# IoT_Greenhouse_V1_0_A_-_Esp32.net
KiCad netlist of a schematic drawn in Altium Designer
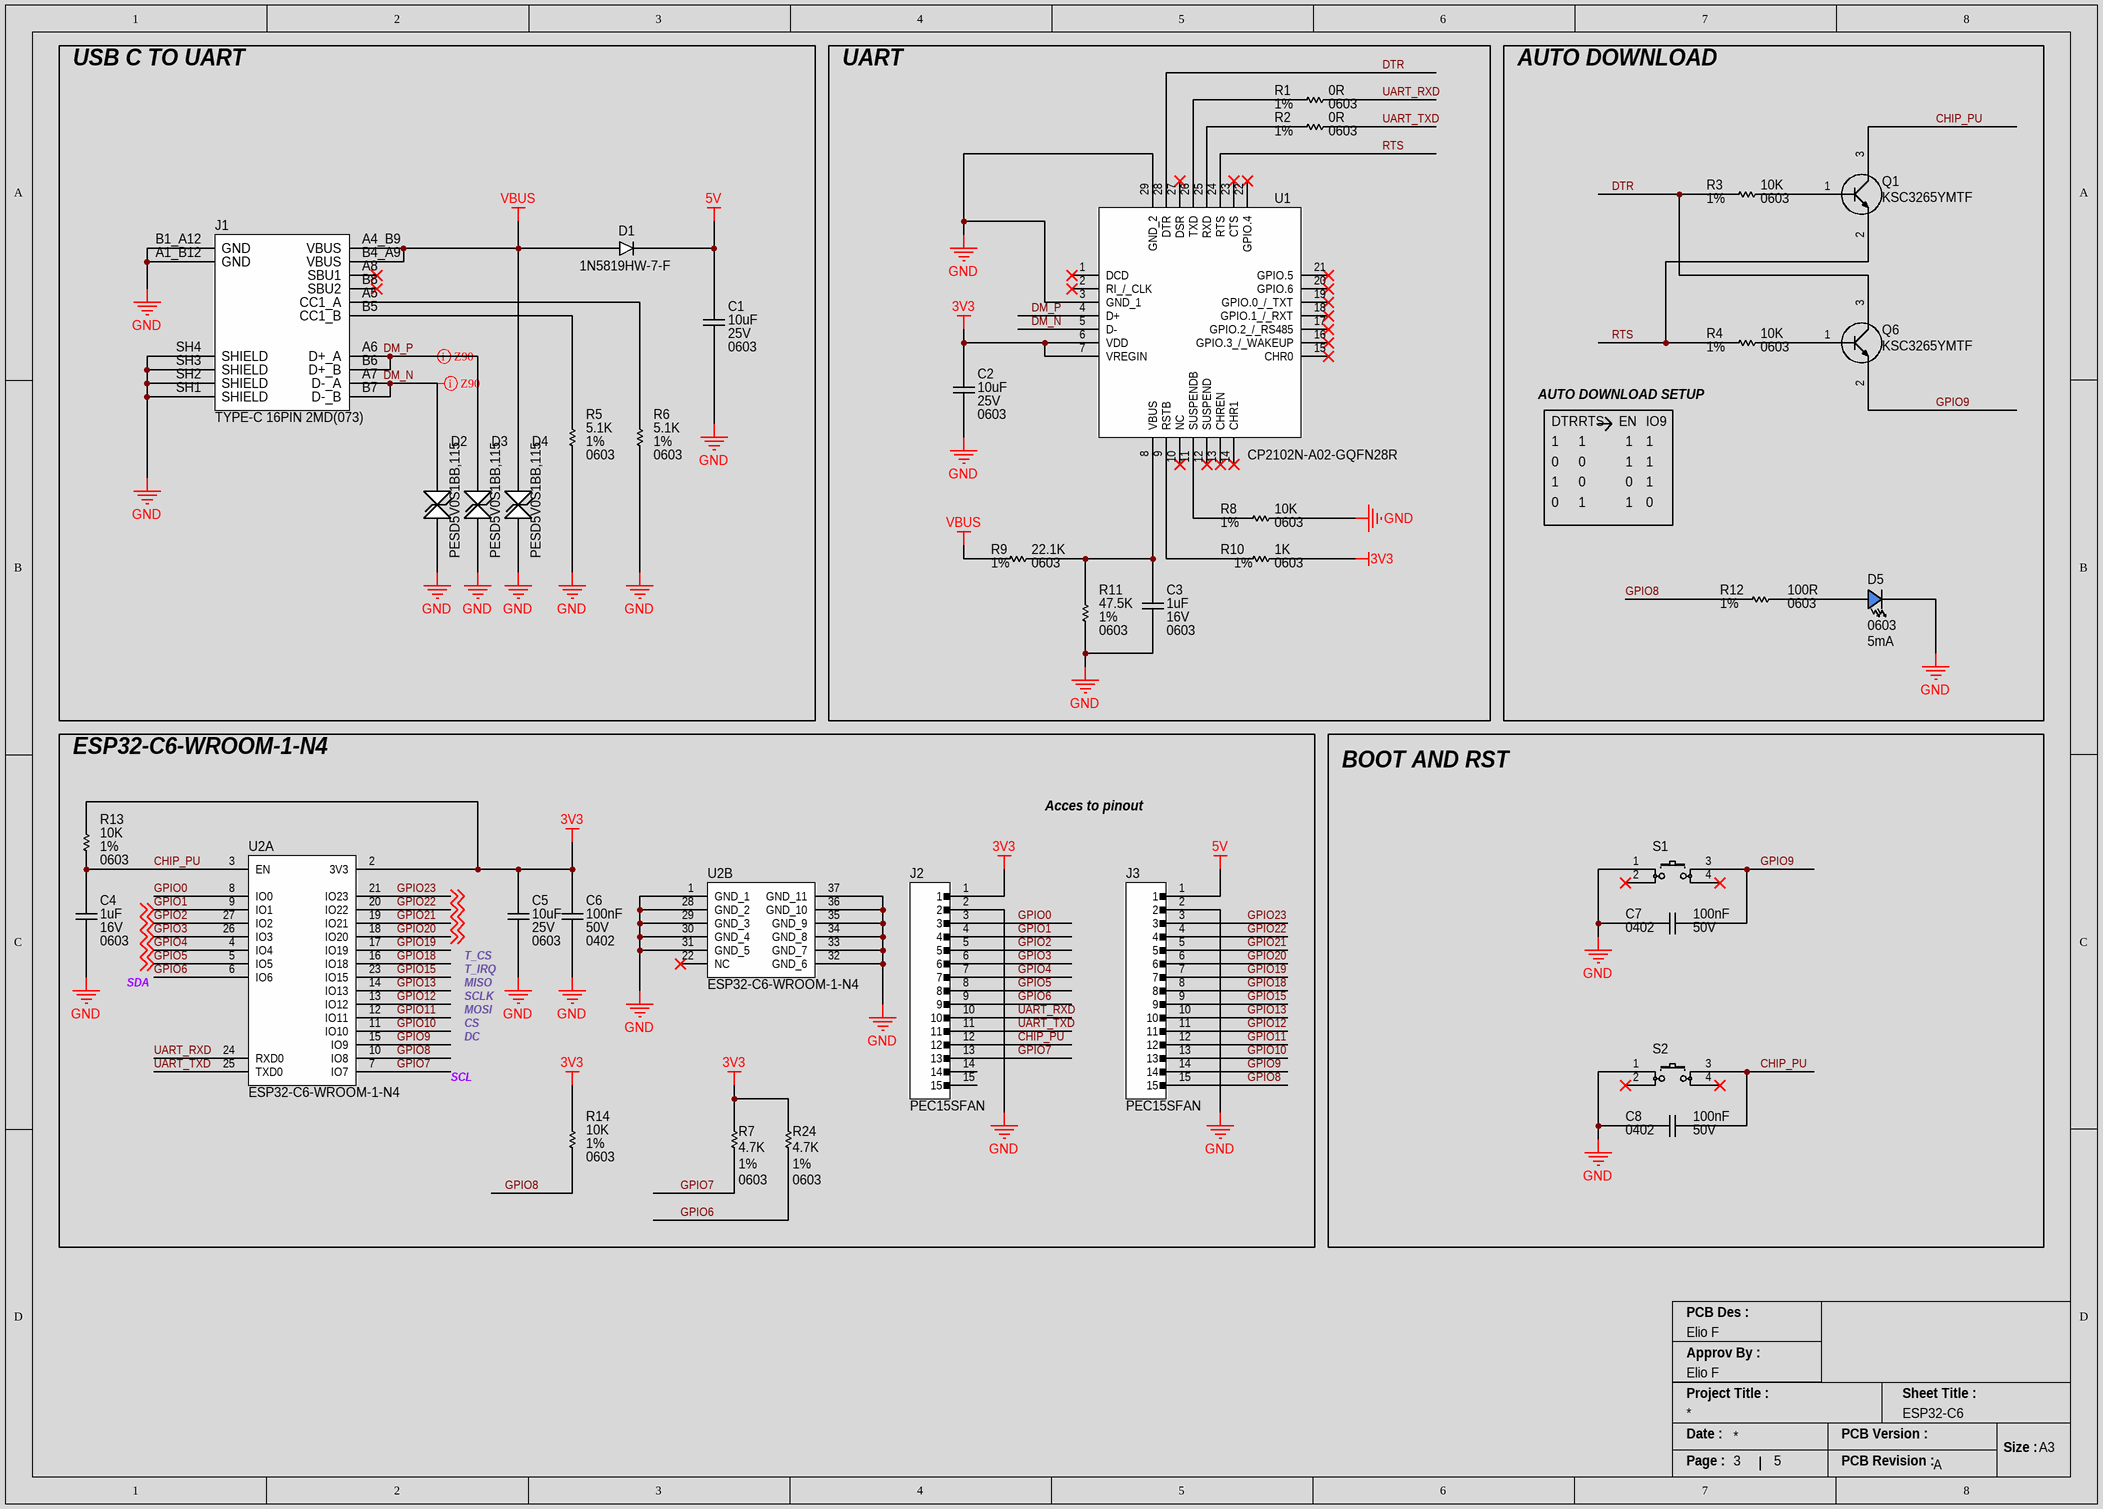
[diagram p0: IoT_Greenhouse V1.0 A - Esp32.SchDoc]

(export (version "E")
  (design (tool "Eeschema 10.0.6"))
  (components
    (comp (ref "C1")
      (value "GRM188R61E106MA73D")
      (footprint "CAP_0603_CAPC1608X08N")
      (description "Multilayer Ceramic Capacitor, 10 uF, 25 V, ± 20%, X5R, 0603 [1608 Metric]")
      (fields
        (field (name "MANUFACTURER") "Murata")
        (field (name "TOLERANCE") "20%")
        (field (name "CASE/PACKAGE") "0603")
        (field (name "CAPACITANCE") "10uF")
        (field (name "VOLTAGE RATING") "25V")
      )
      (libsource (lib "Electronic Devices_LIB") (part "CAP_10UF_25V_X5R_0603"))
    )
    (comp (ref "C2")
      (value "GRM188R61E106MA73D")
      (footprint "CAP_0603_CAPC1608X08N")
      (description "Multilayer Ceramic Capacitor, 10 uF, 25 V, ± 20%, X5R, 0603 [1608 Metric]")
      (fields
        (field (name "MANUFACTURER") "Murata")
        (field (name "TOLERANCE") "20%")
        (field (name "CASE/PACKAGE") "0603")
        (field (name "CAPACITANCE") "10uF")
        (field (name "VOLTAGE RATING") "25V")
      )
      (libsource (lib "Electronic Devices_LIB") (part "CAP_10UF_25V_X5R_0603"))
    )
    (comp (ref "C3")
      (value "CL10A105KO8NNNC")
      (footprint "CAP_0603_CAPC1608X08N")
      (description "CAP CER 1UF 16V X5R 0603")
      (fields
        (field (name "MANUFACTURER") "Samsung")
        (field (name "TOLERANCE") "10%")
        (field (name "VOLTAGE RATING") "16V")
        (field (name "CAPACITANCE") "1uF")
        (field (name "CASE/PACKAGE") "0603")
      )
      (libsource (lib "Electronic Devices_LIB") (part "CAP_1UF_16V_X5R_0603"))
    )
    (comp (ref "C4")
      (value "CL10A105KO8NNNC")
      (footprint "CAP_0603_CAPC1608X08N")
      (description "CAP CER 1UF 16V X5R 0603")
      (fields
        (field (name "MANUFACTURER") "Samsung")
        (field (name "TOLERANCE") "10%")
        (field (name "VOLTAGE RATING") "16V")
        (field (name "CAPACITANCE") "1uF")
        (field (name "CASE/PACKAGE") "0603")
      )
      (libsource (lib "Electronic Devices_LIB") (part "CAP_1UF_16V_X5R_0603"))
    )
    (comp (ref "C5")
      (value "GRM188R61E106MA73D")
      (footprint "CAP_0603_CAPC1608X08N")
      (description "Multilayer Ceramic Capacitor, 10 uF, 25 V, ± 20%, X5R, 0603 [1608 Metric]")
      (fields
        (field (name "MANUFACTURER") "Murata")
        (field (name "TOLERANCE") "20%")
        (field (name "CASE/PACKAGE") "0603")
        (field (name "CAPACITANCE") "10uF")
        (field (name "VOLTAGE RATING") "25V")
      )
      (libsource (lib "Electronic Devices_LIB") (part "CAP_10UF_25V_X5R_0603"))
    )
    (comp (ref "C6")
      (value "GRM155R71H104KE14D")
      (footprint "CAP_0402_CAPC1005X05N")
      (description "Multilayer Ceramic Capacitor, 0.1 uF, 16 V, ± 10%, X7R, 0402 [1005 Metric]")
      (fields
        (field (name "MANUFACTURER") "Murata")
        (field (name "TOLERANCE") "10%")
        (field (name "VOLTAGE RATING") "50V")
        (field (name "CAPACITANCE") "100nF")
        (field (name "CASE/PACKAGE") "0402")
      )
      (libsource (lib "Electronic Devices_LIB") (part "CAP_100NF_50V_X7R_0402"))
    )
    (comp (ref "C7")
      (value "GRM155R71H104KE14D")
      (footprint "CAP_0402_CAPC1005X05N")
      (description "Multilayer Ceramic Capacitor, 0.1 uF, 16 V, ± 10%, X7R, 0402 [1005 Metric]")
      (fields
        (field (name "MANUFACTURER") "Murata")
        (field (name "TOLERANCE") "10%")
        (field (name "VOLTAGE RATING") "50V")
        (field (name "CAPACITANCE") "100nF")
        (field (name "CASE/PACKAGE") "0402")
      )
      (libsource (lib "Electronic Devices_LIB") (part "CAP_100NF_50V_X7R_0402"))
    )
    (comp (ref "C8")
      (value "GRM155R71H104KE14D")
      (footprint "CAP_0402_CAPC1005X05N")
      (description "Multilayer Ceramic Capacitor, 0.1 uF, 16 V, ± 10%, X7R, 0402 [1005 Metric]")
      (fields
        (field (name "MANUFACTURER") "Murata")
        (field (name "TOLERANCE") "10%")
        (field (name "VOLTAGE RATING") "50V")
        (field (name "CAPACITANCE") "100nF")
        (field (name "CASE/PACKAGE") "0402")
      )
      (libsource (lib "Electronic Devices_LIB") (part "CAP_100NF_50V_X7R_0402"))
    )
    (comp (ref "D1")
      (value "1N5819HW-7-F")
      (footprint "DIO_SOD3716X145N")
      (description "Rectifier Diode, Schottky, 1 Phase, 1 Element, 1A, 40V V(RRM), Silicon")
      (fields (field (name "MANUFACTURER") "Diodes"))
      (libsource (lib "Electronic Devices_LIB") (part "DIO_RECT_40V_1A_1N5819HW-7-F"))
    )
    (comp (ref "D2")
      (value "PESD5V0S1BB,115")
      (footprint "DIO_TVS_SODFL1608X65N")
      (description "ESD Suppressor Diode TVS Bi-Dir 5V Automotive 2-Pin SOD-523 T/R / TVS DIODE 5VWM 14VC SOD523")
      (fields (field (name "MANUFACTURER") "Nexperia"))
      (libsource (lib "Electronic Devices_LIB") (part "DIO_TVS_BID_5V_PESD5V0S1BB,115"))
    )
    (comp (ref "D3")
      (value "PESD5V0S1BB,115")
      (footprint "DIO_TVS_SODFL1608X65N")
      (description "ESD Suppressor Diode TVS Bi-Dir 5V Automotive 2-Pin SOD-523 T/R / TVS DIODE 5VWM 14VC SOD523")
      (fields (field (name "MANUFACTURER") "Nexperia"))
      (libsource (lib "Electronic Devices_LIB") (part "DIO_TVS_BID_5V_PESD5V0S1BB,115"))
    )
    (comp (ref "D4")
      (value "PESD5V0S1BB,115")
      (footprint "DIO_TVS_SODFL1608X65N")
      (description "ESD Suppressor Diode TVS Bi-Dir 5V Automotive 2-Pin SOD-523 T/R / TVS DIODE 5VWM 14VC SOD523")
      (fields (field (name "MANUFACTURER") "Nexperia"))
      (libsource (lib "Electronic Devices_LIB") (part "DIO_TVS_BID_5V_PESD5V0S1BB,115"))
    )
    (comp (ref "D5")
      (value "LTST-C193TBKT-5A")
      (footprint "LED_0603-BLUE-0.75mm")
      (description "LED Uni-Color Blue 468nm 2-Pin Chip LED T/R")
      (fields
        (field (name "MANUFACTURER") "Vishay Lite-On")
        (field (name "CASE CODE (IMPERIAL)") "0603")
        (field (name "TEST CURRENT") "5mA")
      )
      (libsource (lib "Electronic Devices_LIB") (part "LED_DIO_BLUE_5mA_0603"))
    )
    (comp (ref "J1")
      (value "TYPE-C 16PIN 2MD(073)")
      (footprint "CONN_USB_C_16P")
      (description "5A 1 Surface Mount 16P Female -25℃~+85℃ Type-C SMD USB Connectors ROHS")
      (fields (field (name "MANUFACTURER") "SHOU HAN"))
      (libsource (lib "Electronic Devices_LIB") (part "CONN_USB_TYPEC_2.0_16P_TYPE-C 16PIN 2MD(073)"))
    )
    (comp (ref "J2")
      (value "PEC15SFAN")
      (footprint "HEADER_MALE_15P")
      (description "CONN HEADER .100 SINGL STR 15POS")
      (fields (field (name "MANUFACTURER") "Sullins"))
      (libsource (lib "Electronic Devices_LIB") (part "CONN_HEADER_MALE_15P_2.54mm"))
    )
    (comp (ref "J3")
      (value "PEC15SFAN")
      (footprint "HEADER_MALE_15P")
      (description "CONN HEADER .100 SINGL STR 15POS")
      (fields (field (name "MANUFACTURER") "Sullins"))
      (libsource (lib "Electronic Devices_LIB") (part "CONN_HEADER_MALE_15P_2.54mm"))
    )
    (comp (ref "Q1")
      (value "KSC3265YMTF")
      (footprint "TRANS_BJT_SOT96P237X111-3N")
      (description "KSC3265 Series 25 V CE Breakdown .8 A NPN Epitaxial Silicon Transistor - SOT-23")
      (fields (field (name "MANUFACTURER") "ON Semiconductor / Fairchild"))
      (libsource (lib "Electronic Devices_LIB") (part "TRANS_BJT_NPN_800mA_25V_KSC3265YMTF"))
    )
    (comp (ref "Q6")
      (value "KSC3265YMTF")
      (footprint "TRANS_BJT_SOT96P237X111-3N")
      (description "KSC3265 Series 25 V CE Breakdown .8 A NPN Epitaxial Silicon Transistor - SOT-23")
      (fields (field (name "MANUFACTURER") "ON Semiconductor / Fairchild"))
      (libsource (lib "Electronic Devices_LIB") (part "TRANS_BJT_NPN_800mA_25V_KSC3265YMTF"))
    )
    (comp (ref "R1")
      (value "RC0603FR-070RL")
      (footprint "RES_0603_RESC1608X04N")
      (description "RC Series 0603 0.1 W 0 Ohm Jumper Surface Mount Thick Film Chip Resistor")
      (fields
        (field (name "MANUFACTURER") "Yageo")
        (field (name "TOLERANCE") "1%")
        (field (name "RESISTANCE") "0R")
        (field (name "CASE CODE (IMPERIAL)") "0603")
      )
      (libsource (lib "Electronic Devices_LIB") (part "RES_0R_1%_100mW_0603"))
    )
    (comp (ref "R2")
      (value "RC0603FR-070RL")
      (footprint "RES_0603_RESC1608X04N")
      (description "RC Series 0603 0.1 W 0 Ohm Jumper Surface Mount Thick Film Chip Resistor")
      (fields
        (field (name "MANUFACTURER") "Yageo")
        (field (name "TOLERANCE") "1%")
        (field (name "RESISTANCE") "0R")
        (field (name "CASE CODE (IMPERIAL)") "0603")
      )
      (libsource (lib "Electronic Devices_LIB") (part "RES_0R_1%_100mW_0603"))
    )
    (comp (ref "R3")
      (value "AC0603FR-1010KL")
      (footprint "RES_0603_RESC1608X04N")
      (description "Chip Resistor Automotive Grade Thick Film 0603 10kOhm 1% Paper T/R")
      (fields
        (field (name "MANUFACTURER") "Yageo")
        (field (name "RESISTANCE") "10K")
        (field (name "TOLERANCE") "1%")
        (field (name "CASE/PACKAGE") "0603")
      )
      (libsource (lib "Electronic Devices_LIB") (part "RES_10K_1%_100mW_0603"))
    )
    (comp (ref "R4")
      (value "AC0603FR-1010KL")
      (footprint "RES_0603_RESC1608X04N")
      (description "Chip Resistor Automotive Grade Thick Film 0603 10kOhm 1% Paper T/R")
      (fields
        (field (name "MANUFACTURER") "Yageo")
        (field (name "RESISTANCE") "10K")
        (field (name "TOLERANCE") "1%")
        (field (name "CASE/PACKAGE") "0603")
      )
      (libsource (lib "Electronic Devices_LIB") (part "RES_10K_1%_100mW_0603"))
    )
    (comp (ref "R5")
      (value "RC0603FR-075K1L")
      (footprint "RES_0603_RESC1608X04N")
      (description "SMD Chip Resistor, 5.1 kOhm, ± 1%, 100 mW, 0603 [1608 Metric], Thick Film, General Purpose")
      (fields
        (field (name "MANUFACTURER") "Yageo")
        (field (name "TOLERANCE") "1%")
        (field (name "RESISTANCE") "5.1K")
        (field (name "CASE/PACKAGE") "0603")
      )
      (libsource (lib "Electronic Devices_LIB") (part "RES_5.1K_1%_100mW_0603"))
    )
    (comp (ref "R6")
      (value "RC0603FR-075K1L")
      (footprint "RES_0603_RESC1608X04N")
      (description "SMD Chip Resistor, 5.1 kOhm, ± 1%, 100 mW, 0603 [1608 Metric], Thick Film, General Purpose")
      (fields
        (field (name "MANUFACTURER") "Yageo")
        (field (name "TOLERANCE") "1%")
        (field (name "RESISTANCE") "5.1K")
        (field (name "CASE/PACKAGE") "0603")
      )
      (libsource (lib "Electronic Devices_LIB") (part "RES_5.1K_1%_100mW_0603"))
    )
    (comp (ref "R7")
      (value "RC0603FR-074K7L")
      (footprint "RES_0603_RESC1608X04N")
      (description "Res Thick Film 0603 4.7K Ohm 1% 1/10W ±100ppm/°C Molded SMD Paper T/R")
      (fields
        (field (name "MANUFACTURER") "Yageo")
        (field (name "RESISTANCE") "4.7K")
        (field (name "TOLERANCE") "1%")
        (field (name "CASE/PACKAGE") "0603")
      )
      (libsource (lib "Electronic Devices_LIB") (part "RES_4.7K_1%_100mW_0603"))
    )
    (comp (ref "R8")
      (value "AC0603FR-1010KL")
      (footprint "RES_0603_RESC1608X04N")
      (description "Chip Resistor Automotive Grade Thick Film 0603 10kOhm 1% Paper T/R")
      (fields
        (field (name "MANUFACTURER") "Yageo")
        (field (name "RESISTANCE") "10K")
        (field (name "TOLERANCE") "1%")
        (field (name "CASE/PACKAGE") "0603")
      )
      (libsource (lib "Electronic Devices_LIB") (part "RES_10K_1%_100mW_0603"))
    )
    (comp (ref "R9")
      (value "RC0603FR-0722K1L")
      (footprint "RES_0603_RESC1608X04N")
      (description "SMD Chip Resistor, 22.1 kOhm, ± 1%, 100 mW, 0603 [1608 Metric], Thick Film, General Purpose")
      (fields
        (field (name "MANUFACTURER") "Yageo")
        (field (name "RESISTANCE") "22.1K")
        (field (name "TOLERANCE") "1%")
        (field (name "CASE/PACKAGE") "0603")
      )
      (libsource (lib "Electronic Devices_LIB") (part "RES_22.1K_1%_100mW_0603"))
    )
    (comp (ref "R10")
      (value "AC0603FR-101KL")
      (footprint "RES_0603_RESC1608X04N")
      (description "Chip Resistor Automotive Grade Thick Film 0603 1kOhm 1% Paper T/R")
      (fields
        (field (name "MANUFACTURER") "Yageo")
        (field (name "RESISTANCE") "1K")
        (field (name "TOLERANCE") "1%")
        (field (name "CASE/PACKAGE") "0603")
      )
      (libsource (lib "Electronic Devices_LIB") (part "RES_1K_1%_100mW_0603"))
    )
    (comp (ref "R11")
      (value "AC0603FR-0747K5L")
      (footprint "RES_0603_RESC1608X04N")
      (description "SMD Chip Resistor, 47.5 kOhm, ± 1%, 100 mW, 0603 [1608 Metric], Thick Film, General Purpose")
      (fields
        (field (name "MANUFACTURER") "Yageo")
        (field (name "TOLERANCE") "1%")
        (field (name "RESISTANCE") "47.5K")
        (field (name "CASE/PACKAGE") "0603")
      )
      (libsource (lib "Electronic Devices_LIB") (part "RES_47.5K_1%_100mW_0603"))
    )
    (comp (ref "R12")
      (value "ERJ3EKF1000V")
      (footprint "CAP_0603_CAPC1608X08N")
      (description "Res Thick Film 0603 100 Ohm 1% 1/10W ±100ppm/°C Molded SMD Punched Carrier T/R")
      (fields
        (field (name "MANUFACTURER") "Panasonic")
        (field (name "CASE CODE (IMPERIAL)") "0603")
        (field (name "TOLERANCE") "1%")
        (field (name "RESISTANCE") "100R")
      )
      (libsource (lib "Electronic Devices_LIB") (part "RES_100R_1%_100MW_0603"))
    )
    (comp (ref "R13")
      (value "AC0603FR-1010KL")
      (footprint "RES_0603_RESC1608X04N")
      (description "Chip Resistor Automotive Grade Thick Film 0603 10kOhm 1% Paper T/R")
      (fields
        (field (name "MANUFACTURER") "Yageo")
        (field (name "RESISTANCE") "10K")
        (field (name "TOLERANCE") "1%")
        (field (name "CASE/PACKAGE") "0603")
      )
      (libsource (lib "Electronic Devices_LIB") (part "RES_10K_1%_100mW_0603"))
    )
    (comp (ref "R14")
      (value "AC0603FR-1010KL")
      (footprint "RES_0603_RESC1608X04N")
      (description "Chip Resistor Automotive Grade Thick Film 0603 10kOhm 1% Paper T/R")
      (fields
        (field (name "MANUFACTURER") "Yageo")
        (field (name "RESISTANCE") "10K")
        (field (name "TOLERANCE") "1%")
        (field (name "CASE/PACKAGE") "0603")
      )
      (libsource (lib "Electronic Devices_LIB") (part "RES_10K_1%_100mW_0603"))
    )
    (comp (ref "R24")
      (value "RC0603FR-074K7L")
      (footprint "RES_0603_RESC1608X04N")
      (description "Res Thick Film 0603 4.7K Ohm 1% 1/10W ±100ppm/°C Molded SMD Paper T/R")
      (fields
        (field (name "MANUFACTURER") "Yageo")
        (field (name "RESISTANCE") "4.7K")
        (field (name "TOLERANCE") "1%")
        (field (name "CASE/PACKAGE") "0603")
      )
      (libsource (lib "Electronic Devices_LIB") (part "RES_4.7K_1%_100mW_0603"))
    )
    (comp (ref "S1")
      (value "PTS526SK15SMTR2LFS")
      (footprint "SWT_NO_PTS526SK15SMTR2LFS")
      (description "Switch Tactile N.O. SPST Round Button Gull Wing 0.05A 12VDC 200000Cycles 2.55N SMD T/R")
      (fields (field (name "MANUFACTURER") "ITT C&K"))
      (libsource (lib "Electronic Devices_LIB") (part "SWITCH_NO_SPST_0.05A"))
    )
    (comp (ref "S2")
      (value "PTS526SK15SMTR2LFS")
      (footprint "SWT_NO_PTS526SK15SMTR2LFS")
      (description "Switch Tactile N.O. SPST Round Button Gull Wing 0.05A 12VDC 200000Cycles 2.55N SMD T/R")
      (fields (field (name "MANUFACTURER") "ITT C&K"))
      (libsource (lib "Electronic Devices_LIB") (part "SWITCH_NO_SPST_0.05A"))
    )
    (comp (ref "U1")
      (value "CP2102N-A02-GQFN28R")
      (footprint "IC_BRIDGE_UART_QFN50P500X500X80-29N-D")
      (description "Full Speed USB to UART Bridge USB 2.0 3.3V T/R Automotive 28-Pin QFN EP")
      (fields (field (name "MANUFACTURER") "Silicon Labs"))
      (libsource (lib "Electronic Devices_LIB") (part "IC_BRIDGE_UART_CP2102N-A02-GQFN28R"))
    )
    (comp (ref "U2")
      (value "ESP32-C6-WROOM-1-N4")
      (footprint "IC_MODULE_ESP32C6WROOM1N4")
      (description "ESP32-C6-WROOM-1-N4 Engineering Module - 4 MB Quad SPI Flash")
      (fields (field (name "MANUFACTURER") "Espressif Systems"))
      (libsource (lib "Electronic Devices_LIB") (part "IC_MODULE_ESP32-C6-WROOM-1-N4"))
    )
  )
  (nets
    (net (code "1") (name "/CHIP_PU") (class "Default")
      (node (ref "C4") (pin "2") (pinfunction "2_2") (pintype "passive"))
      (node (ref "C8") (pin "1") (pinfunction "1_1") (pintype "passive"))
      (node (ref "J2") (pin "12") (pinfunction "12_12") (pintype "passive"))
      (node (ref "Q1") (pin "3") (pinfunction "C_3") (pintype "passive"))
      (node (ref "R13") (pin "2") (pinfunction "2_2") (pintype "passive"))
      (node (ref "S2") (pin "3") (pinfunction "NO1_3") (pintype "passive"))
      (node (ref "U2") (pin "3") (pinfunction "EN_3") (pintype "passive"))
    )
    (net (code "2") (name "/DM_N") (class "Default")
      (node (ref "D2") (pin "2") (pinfunction "K2_2") (pintype "passive"))
      (node (ref "J1") (pin "A7") (pinfunction "D-_A_A7") (pintype "passive"))
      (node (ref "J1") (pin "B7") (pinfunction "D-_B_B7") (pintype "passive"))
      (node (ref "U1") (pin "5") (pinfunction "D-_5") (pintype "passive"))
    )
    (net (code "3") (name "/DM_P") (class "Default")
      (node (ref "D3") (pin "2") (pinfunction "K2_2") (pintype "passive"))
      (node (ref "J1") (pin "A6") (pinfunction "D+_A_A6") (pintype "passive"))
      (node (ref "J1") (pin "B6") (pinfunction "D+_B_B6") (pintype "passive"))
      (node (ref "U1") (pin "4") (pinfunction "D+_4") (pintype "passive"))
    )
    (net (code "4") (name "/DTR") (class "Default")
      (node (ref "Q6") (pin "3") (pinfunction "C_3") (pintype "passive"))
      (node (ref "R3") (pin "2") (pinfunction "2_2") (pintype "passive"))
      (node (ref "U1") (pin "28") (pinfunction "DTR_28") (pintype "passive"))
    )
    (net (code "5") (name "/GPIO0") (class "Default")
      (node (ref "J2") (pin "3") (pinfunction "3_3") (pintype "passive"))
      (node (ref "U2") (pin "8") (pinfunction "IO0_8") (pintype "passive"))
    )
    (net (code "6") (name "/GPIO1") (class "Default")
      (node (ref "J2") (pin "4") (pinfunction "4_4") (pintype "passive"))
      (node (ref "J2") (pin "5") (pinfunction "5_5") (pintype "passive"))
      (node (ref "J2") (pin "6") (pinfunction "6_6") (pintype "passive"))
      (node (ref "J2") (pin "7") (pinfunction "7_7") (pintype "passive"))
      (node (ref "J2") (pin "8") (pinfunction "8_8") (pintype "passive"))
      (node (ref "J3") (pin "3") (pinfunction "3_3") (pintype "passive"))
      (node (ref "J3") (pin "4") (pinfunction "4_4") (pintype "passive"))
      (node (ref "J3") (pin "5") (pinfunction "5_5") (pintype "passive"))
      (node (ref "J3") (pin "6") (pinfunction "6_6") (pintype "passive"))
      (node (ref "U2") (pin "18") (pinfunction "IO20_18") (pintype "passive"))
      (node (ref "U2") (pin "19") (pinfunction "IO21_19") (pintype "passive"))
      (node (ref "U2") (pin "20") (pinfunction "IO22_20") (pintype "passive"))
      (node (ref "U2") (pin "21") (pinfunction "IO23_21") (pintype "passive"))
      (node (ref "U2") (pin "26") (pinfunction "IO3_26") (pintype "passive"))
      (node (ref "U2") (pin "27") (pinfunction "IO2_27") (pintype "passive"))
      (node (ref "U2") (pin "4") (pinfunction "IO4_4") (pintype "passive"))
      (node (ref "U2") (pin "5") (pinfunction "IO5_5") (pintype "passive"))
      (node (ref "U2") (pin "9") (pinfunction "IO1_9") (pintype "passive"))
    )
    (net (code "7") (name "/GPIO6") (class "Default")
      (node (ref "J2") (pin "9") (pinfunction "9_9") (pintype "passive"))
      (node (ref "R24") (pin "1") (pinfunction "1_1") (pintype "passive"))
      (node (ref "U2") (pin "6") (pinfunction "IO6_6") (pintype "passive"))
    )
    (net (code "8") (name "/GPIO7") (class "Default")
      (node (ref "J2") (pin "13") (pinfunction "13_13") (pintype "passive"))
      (node (ref "R7") (pin "1") (pinfunction "1_1") (pintype "passive"))
      (node (ref "U2") (pin "7") (pinfunction "IO7_7") (pintype "passive"))
    )
    (net (code "9") (name "/GPIO8") (class "Default")
      (node (ref "J3") (pin "15") (pinfunction "15_15") (pintype "passive"))
      (node (ref "R12") (pin "1") (pinfunction "1_1") (pintype "passive"))
      (node (ref "R14") (pin "2") (pinfunction "2_2") (pintype "passive"))
      (node (ref "U2") (pin "10") (pinfunction "IO8_10") (pintype "passive"))
    )
    (net (code "10") (name "/GPIO9") (class "Default")
      (node (ref "C7") (pin "1") (pinfunction "1_1") (pintype "passive"))
      (node (ref "J3") (pin "14") (pinfunction "14_14") (pintype "passive"))
      (node (ref "Q6") (pin "2") (pinfunction "E_2") (pintype "passive"))
      (node (ref "S1") (pin "3") (pinfunction "NO1_3") (pintype "passive"))
      (node (ref "U2") (pin "15") (pinfunction "IO9_15") (pintype "passive"))
    )
    (net (code "11") (name "/GPIO10") (class "Default")
      (node (ref "J3") (pin "13") (pinfunction "13_13") (pintype "passive"))
      (node (ref "U2") (pin "11") (pinfunction "IO10_11") (pintype "passive"))
    )
    (net (code "12") (name "/GPIO11") (class "Default")
      (node (ref "J3") (pin "12") (pinfunction "12_12") (pintype "passive"))
      (node (ref "U2") (pin "12") (pinfunction "IO11_12") (pintype "passive"))
    )
    (net (code "13") (name "/GPIO12") (class "Default")
      (node (ref "J3") (pin "11") (pinfunction "11_11") (pintype "passive"))
      (node (ref "U2") (pin "13") (pinfunction "IO12_13") (pintype "passive"))
    )
    (net (code "14") (name "/GPIO13") (class "Default")
      (node (ref "J3") (pin "10") (pinfunction "10_10") (pintype "passive"))
      (node (ref "U2") (pin "14") (pinfunction "IO13_14") (pintype "passive"))
    )
    (net (code "15") (name "/GPIO15") (class "Default")
      (node (ref "J3") (pin "9") (pinfunction "9_9") (pintype "passive"))
      (node (ref "U2") (pin "23") (pinfunction "IO15_23") (pintype "passive"))
    )
    (net (code "16") (name "/GPIO18") (class "Default")
      (node (ref "J3") (pin "8") (pinfunction "8_8") (pintype "passive"))
      (node (ref "U2") (pin "16") (pinfunction "IO18_16") (pintype "passive"))
    )
    (net (code "17") (name "/GPIO19") (class "Default")
      (node (ref "J3") (pin "7") (pinfunction "7_7") (pintype "passive"))
      (node (ref "U2") (pin "17") (pinfunction "IO19_17") (pintype "passive"))
    )
    (net (code "18") (name "/RTS") (class "Default")
      (node (ref "Q1") (pin "2") (pinfunction "E_2") (pintype "passive"))
      (node (ref "R4") (pin "2") (pinfunction "2_2") (pintype "passive"))
      (node (ref "U1") (pin "24") (pinfunction "RTS_24") (pintype "passive"))
    )
    (net (code "19") (name "/UART_RXD") (class "Default")
      (node (ref "J2") (pin "10") (pinfunction "10_10") (pintype "passive"))
      (node (ref "R1") (pin "1") (pinfunction "1_1") (pintype "passive"))
      (node (ref "U2") (pin "24") (pinfunction "RXD0_24") (pintype "passive"))
    )
    (net (code "20") (name "/UART_TXD") (class "Default")
      (node (ref "J2") (pin "11") (pinfunction "11_11") (pintype "passive"))
      (node (ref "R2") (pin "1") (pinfunction "1_1") (pintype "passive"))
      (node (ref "U2") (pin "25") (pinfunction "TXD0_25") (pintype "passive"))
    )
    (net (code "21") (name "3V3") (class "Default")
      (node (ref "C2") (pin "2") (pinfunction "2_2") (pintype "passive"))
      (node (ref "C5") (pin "2") (pinfunction "2_2") (pintype "passive"))
      (node (ref "C6") (pin "2") (pinfunction "2_2") (pintype "passive"))
      (node (ref "J2") (pin "1") (pinfunction "1_1") (pintype "passive"))
      (node (ref "R10") (pin "2") (pinfunction "2_2") (pintype "passive"))
      (node (ref "R13") (pin "1") (pinfunction "1_1") (pintype "passive"))
      (node (ref "R14") (pin "1") (pinfunction "1_1") (pintype "passive"))
      (node (ref "R24") (pin "2") (pinfunction "2_2") (pintype "passive"))
      (node (ref "R7") (pin "2") (pinfunction "2_2") (pintype "passive"))
      (node (ref "U1") (pin "6") (pinfunction "VDD_6") (pintype "passive"))
      (node (ref "U1") (pin "7") (pinfunction "VREGIN_7") (pintype "passive"))
      (node (ref "U2") (pin "2") (pinfunction "3V3_2") (pintype "passive"))
    )
    (net (code "22") (name "5V") (class "Default")
      (node (ref "C1") (pin "2") (pinfunction "2_2") (pintype "passive"))
      (node (ref "D1") (pin "1") (pinfunction "K_1") (pintype "passive"))
      (node (ref "J3") (pin "1") (pinfunction "1_1") (pintype "passive"))
    )
    (net (code "23") (name "GND") (class "Default")
      (node (ref "C1") (pin "1") (pinfunction "1_1") (pintype "passive"))
      (node (ref "C2") (pin "1") (pinfunction "1_1") (pintype "passive"))
      (node (ref "C3") (pin "1") (pinfunction "1_1") (pintype "passive"))
      (node (ref "C4") (pin "1") (pinfunction "1_1") (pintype "passive"))
      (node (ref "C5") (pin "1") (pinfunction "1_1") (pintype "passive"))
      (node (ref "C6") (pin "1") (pinfunction "1_1") (pintype "passive"))
      (node (ref "C7") (pin "2") (pinfunction "2_2") (pintype "passive"))
      (node (ref "C8") (pin "2") (pinfunction "2_2") (pintype "passive"))
      (node (ref "D2") (pin "1") (pinfunction "K1_1") (pintype "passive"))
      (node (ref "D3") (pin "1") (pinfunction "K1_1") (pintype "passive"))
      (node (ref "D4") (pin "1") (pinfunction "K1_1") (pintype "passive"))
      (node (ref "D5") (pin "1") (pinfunction "C_1") (pintype "passive"))
      (node (ref "J1") (pin "A1_B12") (pinfunction "GND_A1_B12") (pintype "power_in"))
      (node (ref "J1") (pin "B1_A12") (pinfunction "GND_B1_A12") (pintype "power_in"))
      (node (ref "J1") (pin "SH1") (pinfunction "SHIELD_SH1") (pintype "passive"))
      (node (ref "J1") (pin "SH2") (pinfunction "SHIELD_SH2") (pintype "passive"))
      (node (ref "J1") (pin "SH3") (pinfunction "SHIELD_SH3") (pintype "passive"))
      (node (ref "J1") (pin "SH4") (pinfunction "SHIELD_SH4") (pintype "passive"))
      (node (ref "J2") (pin "2") (pinfunction "2_2") (pintype "passive"))
      (node (ref "J3") (pin "2") (pinfunction "2_2") (pintype "passive"))
      (node (ref "R11") (pin "1") (pinfunction "1_1") (pintype "passive"))
      (node (ref "R5") (pin "1") (pinfunction "1_1") (pintype "passive"))
      (node (ref "R6") (pin "1") (pinfunction "1_1") (pintype "passive"))
      (node (ref "R8") (pin "2") (pinfunction "2_2") (pintype "passive"))
      (node (ref "S1") (pin "1") (pinfunction "COM_1_1") (pintype "passive"))
      (node (ref "S2") (pin "1") (pinfunction "COM_1_1") (pintype "passive"))
      (node (ref "U1") (pin "29") (pinfunction "GND_2_29") (pintype "passive"))
      (node (ref "U1") (pin "3") (pinfunction "GND_1_3") (pintype "passive"))
      (node (ref "U2") (pin "1") (pinfunction "GND_1_1") (pintype "passive"))
      (node (ref "U2") (pin "28") (pinfunction "GND_2_28") (pintype "passive"))
      (node (ref "U2") (pin "29") (pinfunction "GND_3_29") (pintype "passive"))
      (node (ref "U2") (pin "30") (pinfunction "GND_4_30") (pintype "passive"))
      (node (ref "U2") (pin "31") (pinfunction "GND_5_31") (pintype "passive"))
      (node (ref "U2") (pin "32") (pinfunction "GND_6_32") (pintype "passive"))
      (node (ref "U2") (pin "33") (pinfunction "GND_7_33") (pintype "passive"))
      (node (ref "U2") (pin "34") (pinfunction "GND_8_34") (pintype "passive"))
      (node (ref "U2") (pin "35") (pinfunction "GND_9_35") (pintype "passive"))
      (node (ref "U2") (pin "36") (pinfunction "GND_10_36") (pintype "passive"))
      (node (ref "U2") (pin "37") (pinfunction "GND_11_37") (pintype "passive"))
    )
    (net (code "24") (name "Net-(D5-A)") (class "Default")
      (node (ref "D5") (pin "2") (pinfunction "A_2") (pintype "passive"))
      (node (ref "R12") (pin "2") (pinfunction "2_2") (pintype "passive"))
    )
    (net (code "25") (name "Net-(J1-CC1_A)") (class "Default")
      (node (ref "J1") (pin "A5") (pinfunction "CC1_A_A5") (pintype "passive"))
      (node (ref "R6") (pin "2") (pinfunction "2_2") (pintype "passive"))
    )
    (net (code "26") (name "Net-(J1-CC1_B)") (class "Default")
      (node (ref "J1") (pin "B5") (pinfunction "CC1_B_B5") (pintype "passive"))
      (node (ref "R5") (pin "2") (pinfunction "2_2") (pintype "passive"))
    )
    (net (code "27") (name "Net-(Q1-B)") (class "Default")
      (node (ref "Q1") (pin "1") (pinfunction "B_1") (pintype "passive"))
      (node (ref "R3") (pin "1") (pinfunction "1_1") (pintype "passive"))
    )
    (net (code "28") (name "Net-(Q6-B)") (class "Default")
      (node (ref "Q6") (pin "1") (pinfunction "B_1") (pintype "passive"))
      (node (ref "R4") (pin "1") (pinfunction "1_1") (pintype "passive"))
    )
    (net (code "29") (name "Net-(U1-RSTB)") (class "Default")
      (node (ref "R10") (pin "1") (pinfunction "1_1") (pintype "passive"))
      (node (ref "U1") (pin "9") (pinfunction "RSTB_9") (pintype "passive"))
    )
    (net (code "30") (name "Net-(U1-RXD)") (class "Default")
      (node (ref "R2") (pin "2") (pinfunction "2_2") (pintype "passive"))
      (node (ref "U1") (pin "25") (pinfunction "RXD_25") (pintype "passive"))
    )
    (net (code "31") (name "Net-(U1-SUSPENDB)") (class "Default")
      (node (ref "R8") (pin "1") (pinfunction "1_1") (pintype "passive"))
      (node (ref "U1") (pin "11") (pinfunction "SUSPENDB_11") (pintype "passive"))
    )
    (net (code "32") (name "Net-(U1-TXD)") (class "Default")
      (node (ref "R1") (pin "2") (pinfunction "2_2") (pintype "passive"))
      (node (ref "U1") (pin "26") (pinfunction "TXD_26") (pintype "passive"))
    )
    (net (code "33") (name "Net-(U1-VBUS)") (class "Default")
      (node (ref "C3") (pin "2") (pinfunction "2_2") (pintype "passive"))
      (node (ref "R11") (pin "2") (pinfunction "2_2") (pintype "passive"))
      (node (ref "R9") (pin "2") (pinfunction "2_2") (pintype "passive"))
      (node (ref "U1") (pin "8") (pinfunction "VBUS_8") (pintype "passive"))
    )
    (net (code "34") (name "VBUS") (class "Default")
      (node (ref "D1") (pin "2") (pinfunction "A_2") (pintype "passive"))
      (node (ref "D4") (pin "2") (pinfunction "K2_2") (pintype "passive"))
      (node (ref "J1") (pin "A4_B9") (pinfunction "VBUS_A4_B9") (pintype "power_in"))
      (node (ref "J1") (pin "B4_A9") (pinfunction "VBUS_B4_A9") (pintype "power_in"))
      (node (ref "R9") (pin "1") (pinfunction "1_1") (pintype "passive"))
    )
    (net (code "35") (name "unconnected-(J1-SBU1-PadA8)") (class "Default")
      (node (ref "J1") (pin "A8") (pinfunction "SBU1_A8") (pintype "passive+no_connect"))
    )
    (net (code "36") (name "unconnected-(J1-SBU2-PadB8)") (class "Default")
      (node (ref "J1") (pin "B8") (pinfunction "SBU2_B8") (pintype "passive+no_connect"))
    )
    (net (code "37") (name "unconnected-(J2-Pad14)") (class "Default")
      (node (ref "J2") (pin "14") (pinfunction "14_14") (pintype "passive"))
    )
    (net (code "38") (name "unconnected-(J2-Pad15)") (class "Default")
      (node (ref "J2") (pin "15") (pinfunction "15_15") (pintype "passive"))
    )
    (net (code "39") (name "unconnected-(S1-COM2-Pad2)") (class "Default")
      (node (ref "S1") (pin "2") (pinfunction "COM2_2") (pintype "passive+no_connect"))
    )
    (net (code "40") (name "unconnected-(S1-NO2-Pad4)") (class "Default")
      (node (ref "S1") (pin "4") (pinfunction "NO2_4") (pintype "passive+no_connect"))
    )
    (net (code "41") (name "unconnected-(S2-COM2-Pad2)") (class "Default")
      (node (ref "S2") (pin "2") (pinfunction "COM2_2") (pintype "passive+no_connect"))
    )
    (net (code "42") (name "unconnected-(S2-NO2-Pad4)") (class "Default")
      (node (ref "S2") (pin "4") (pinfunction "NO2_4") (pintype "passive+no_connect"))
    )
    (net (code "43") (name "unconnected-(U1-CHR0-Pad15)") (class "Default")
      (node (ref "U1") (pin "15") (pinfunction "CHR0_15") (pintype "passive+no_connect"))
    )
    (net (code "44") (name "unconnected-(U1-CHR1-Pad14)") (class "Default")
      (node (ref "U1") (pin "14") (pinfunction "CHR1_14") (pintype "passive+no_connect"))
    )
    (net (code "45") (name "unconnected-(U1-CHREN-Pad13)") (class "Default")
      (node (ref "U1") (pin "13") (pinfunction "CHREN_13") (pintype "passive+no_connect"))
    )
    (net (code "46") (name "unconnected-(U1-CTS-Pad23)") (class "Default")
      (node (ref "U1") (pin "23") (pinfunction "CTS_23") (pintype "passive+no_connect"))
    )
    (net (code "47") (name "unconnected-(U1-DCD-Pad1)") (class "Default")
      (node (ref "U1") (pin "1") (pinfunction "DCD_1") (pintype "passive+no_connect"))
    )
    (net (code "48") (name "unconnected-(U1-DSR-Pad27)") (class "Default")
      (node (ref "U1") (pin "27") (pinfunction "DSR_27") (pintype "passive+no_connect"))
    )
    (net (code "49") (name "unconnected-(U1-GPIO.0_{slash}_TXT-Pad19)") (class "Default")
      (node (ref "U1") (pin "19") (pinfunction "GPIO.0_/_TXT_19") (pintype "passive+no_connect"))
    )
    (net (code "50") (name "unconnected-(U1-GPIO.1_{slash}_RXT-Pad18)") (class "Default")
      (node (ref "U1") (pin "18") (pinfunction "GPIO.1_/_RXT_18") (pintype "passive+no_connect"))
    )
    (net (code "51") (name "unconnected-(U1-GPIO.2_{slash}_RS485-Pad17)") (class "Default")
      (node (ref "U1") (pin "17") (pinfunction "GPIO.2_/_RS485_17") (pintype "passive+no_connect"))
    )
    (net (code "52") (name "unconnected-(U1-GPIO.3_{slash}_WAKEUP-Pad16)") (class "Default")
      (node (ref "U1") (pin "16") (pinfunction "GPIO.3_/_WAKEUP_16") (pintype "passive+no_connect"))
    )
    (net (code "53") (name "unconnected-(U1-GPIO.4-Pad22)") (class "Default")
      (node (ref "U1") (pin "22") (pinfunction "GPIO.4_22") (pintype "passive+no_connect"))
    )
    (net (code "54") (name "unconnected-(U1-GPIO.5-Pad21)") (class "Default")
      (node (ref "U1") (pin "21") (pinfunction "GPIO.5_21") (pintype "passive+no_connect"))
    )
    (net (code "55") (name "unconnected-(U1-GPIO.6-Pad20)") (class "Default")
      (node (ref "U1") (pin "20") (pinfunction "GPIO.6_20") (pintype "passive+no_connect"))
    )
    (net (code "56") (name "unconnected-(U1-NC-Pad10)") (class "Default")
      (node (ref "U1") (pin "10") (pinfunction "NC_10") (pintype "passive+no_connect"))
    )
    (net (code "57") (name "unconnected-(U1-RI_{slash}_CLK-Pad2)") (class "Default")
      (node (ref "U1") (pin "2") (pinfunction "RI_/_CLK_2") (pintype "passive+no_connect"))
    )
    (net (code "58") (name "unconnected-(U1-SUSPEND-Pad12)") (class "Default")
      (node (ref "U1") (pin "12") (pinfunction "SUSPEND_12") (pintype "passive+no_connect"))
    )
    (net (code "59") (name "unconnected-(U2B-NC-Pad22)") (class "Default")
      (node (ref "U2") (pin "22") (pinfunction "NC_22") (pintype "passive+no_connect"))
    )
  )
)
